# MAGI_sUSBCore.net
KiCad netlist of a schematic drawn in Altium Designer
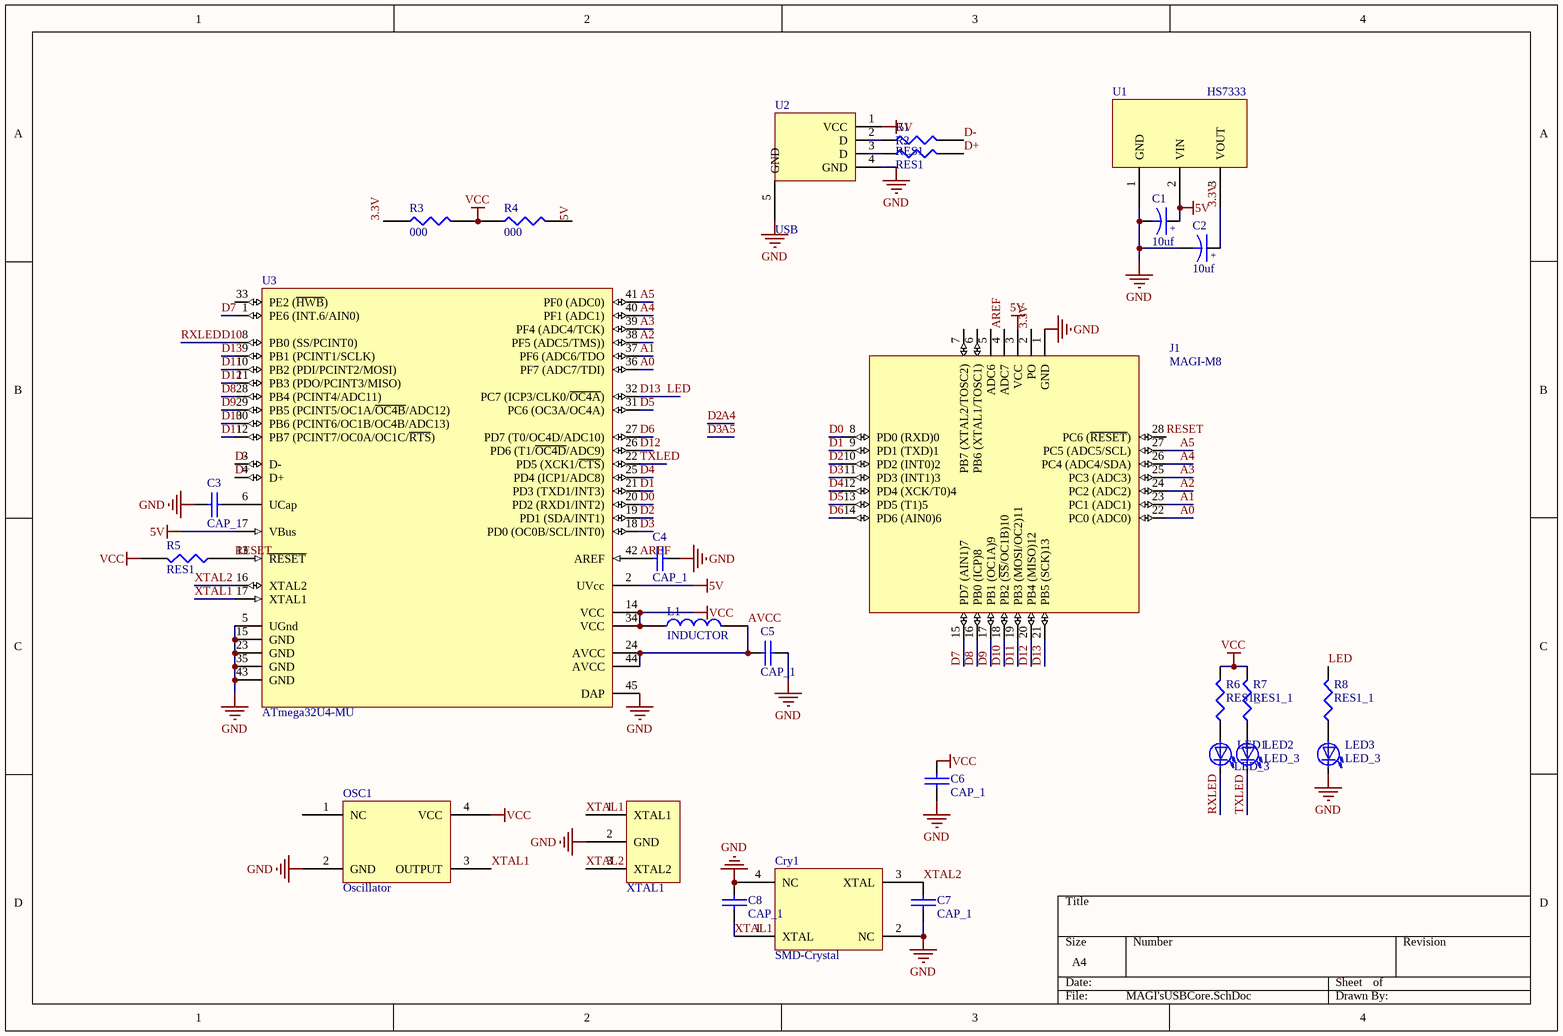
[diagram p0: MAGI'sUSBCore.SchDoc]

(export (version "E")
  (design (tool "Eeschema 10.0.6"))
  (components
    (comp (ref "C1")
      (value "10uf")
      (footprint "6-0805_N")
      (description "Capacitor")
      (libsource (lib "电容器") (part "CAPACITOR POL"))
    )
    (comp (ref "C2")
      (value "10uf")
      (footprint "6-0805_N")
      (description "Capacitor")
      (libsource (lib "电容器") (part "CAPACITOR POL"))
    )
    (comp (ref "C3")
      (value "CAP_1")
      (footprint "6-0805_N")
      (description "Capacitor")
      (libsource (lib "电容器") (part "CAP_1"))
    )
    (comp (ref "C4")
      (value "CAP_1")
      (footprint "6-0805_N")
      (description "Capacitor")
      (libsource (lib "电容器") (part "CAP_1"))
    )
    (comp (ref "C5")
      (value "CAP_1")
      (footprint "6-0805_N")
      (description "Capacitor")
      (libsource (lib "电容器") (part "CAP_1"))
    )
    (comp (ref "C6")
      (value "CAP_1")
      (footprint "C1210_N")
      (description "Capacitor")
      (libsource (lib "电容器") (part "CAP_1"))
    )
    (comp (ref "C7")
      (value "CAP_1")
      (footprint "1608[0603]")
      (description "Capacitor")
      (libsource (lib "电容器") (part "CAP_1"))
    )
    (comp (ref "C8")
      (value "CAP_1")
      (footprint "1608[0603]")
      (description "Capacitor")
      (libsource (lib "电容器") (part "CAP_1"))
    )
    (comp (ref "Cry1") (value "SMD-Crystal") (footprint "3225") (libsource (lib "XTAL") (part "Crystal")))
    (comp (ref "J1") (value "MAGI-M8") (footprint "MAGI-M8") (libsource (lib "MAGI-M8") (part "MAGI-M8")))
    (comp (ref "L1") (value "INDUCTOR") (footprint "C1210_N") (libsource (lib "汇总") (part "INDUCTOR")))
    (comp (ref "LED1") (value "LED_3") (footprint "6-0805_N") (libsource (lib "二极管") (part "LED_3")))
    (comp (ref "LED2") (value "LED_3") (footprint "6-0805_N") (libsource (lib "二极管") (part "LED_3")))
    (comp (ref "LED3") (value "LED_3") (footprint "6-0805_N") (libsource (lib "二极管") (part "LED_3")))
    (comp (ref "OSC1")
      (value "Oscillator")
      (footprint "Oscillator")
      (libsource (lib "XTAL") (part "Oscillator"))
    )
    (comp (ref "R1") (value "RES1") (footprint "6-0805_N") (libsource (lib "电阻器") (part "RES1")))
    (comp (ref "R2") (value "RES1") (footprint "6-0805_N") (libsource (lib "电阻器") (part "RES1")))
    (comp (ref "R3") (value "000") (footprint "6-0805_N") (libsource (lib "电阻器") (part "RES1")))
    (comp (ref "R4") (value "000") (footprint "6-0805_N") (libsource (lib "电阻器") (part "RES1")))
    (comp (ref "R5") (value "RES1") (footprint "6-0805_N") (libsource (lib "电阻器") (part "RES1")))
    (comp (ref "R6") (value "RES1_1") (footprint "6-0805_N") (libsource (lib "电阻器") (part "RES1_1")))
    (comp (ref "R7") (value "RES1_1") (footprint "6-0805_N") (libsource (lib "电阻器") (part "RES1_1")))
    (comp (ref "R8") (value "RES1_1") (footprint "6-0805_N") (libsource (lib "电阻器") (part "RES1_1")))
    (comp (ref "U1") (value "HS7333") (footprint "HS7333") (libsource (lib "PMIC") (part "HS7333")))
    (comp (ref "U2") (value "USB") (footprint "MicroUSB") (libsource (lib "USB接口") (part "USB")))
    (comp (ref "U3")
      (value "ATmega32U4-MU")
      (footprint "44PW_N")
      (fields (field (name "PUBLISHER") "Altium Limited"))
      (libsource (lib "Atmel Microcontroller 8-Bit megaAVR") (part "ATmega32U4-MU"))
    )
    (comp (ref "XTAL1")
      (value "CSTCE16M00G53")
      (footprint "CSTCE_V")
      (libsource (lib "XTAL") (part "CSTCE16M00G53"))
    )
  )
  (nets
    (net (code "1") (name "/3.3V") (class "Default")
      (node (ref "C2") (pin "1") (pinfunction "1_1") (pintype "passive"))
      (node (ref "J1") (pin "2") (pinfunction "PO_2") (pintype "power_in"))
      (node (ref "R3") (pin "1") (pinfunction "1_1") (pintype "passive"))
      (node (ref "U1") (pin "3") (pinfunction "VOUT_3") (pintype "passive"))
    )
    (net (code "2") (name "/A0") (class "Default")
      (node (ref "J1") (pin "22") (pinfunction "PC0_(ADC0)_22") (pintype "bidirectional"))
      (node (ref "U3") (pin "36") (pinfunction "PF7_(ADC7/TDI)_36") (pintype "bidirectional"))
    )
    (net (code "3") (name "/A1") (class "Default")
      (node (ref "J1") (pin "23") (pinfunction "PC1_(ADC1)_23") (pintype "bidirectional"))
      (node (ref "U3") (pin "37") (pinfunction "PF6_(ADC6/TDO_37") (pintype "bidirectional"))
    )
    (net (code "4") (name "/A2") (class "Default")
      (node (ref "J1") (pin "24") (pinfunction "PC2_(ADC2)_24") (pintype "bidirectional"))
      (node (ref "U3") (pin "38") (pinfunction "PF5_(ADC5/TMS))_38") (pintype "bidirectional"))
    )
    (net (code "5") (name "/A3") (class "Default")
      (node (ref "J1") (pin "25") (pinfunction "PC3_(ADC3)_25") (pintype "bidirectional"))
      (node (ref "U3") (pin "39") (pinfunction "PF4_(ADC4/TCK)_39") (pintype "bidirectional"))
    )
    (net (code "6") (name "/A4") (class "Default")
      (node (ref "J1") (pin "10") (pinfunction "PD2_(INT0)2_10") (pintype "bidirectional"))
      (node (ref "J1") (pin "26") (pinfunction "PC4_(ADC4/SDA)_26") (pintype "bidirectional"))
      (node (ref "U3") (pin "19") (pinfunction "PD1_(SDA/INT1)_19") (pintype "bidirectional"))
      (node (ref "U3") (pin "40") (pinfunction "PF1_(ADC1)_40") (pintype "bidirectional"))
    )
    (net (code "7") (name "/A5") (class "Default")
      (node (ref "J1") (pin "11") (pinfunction "PD3_(INT1)3_11") (pintype "bidirectional"))
      (node (ref "J1") (pin "27") (pinfunction "PC5_(ADC5/SCL)_27") (pintype "bidirectional"))
      (node (ref "U3") (pin "18") (pinfunction "PD0_(OC0B/SCL/INT0)_18") (pintype "bidirectional"))
      (node (ref "U3") (pin "41") (pinfunction "PF0_(ADC0)_41") (pintype "bidirectional"))
    )
    (net (code "8") (name "/AREF") (class "Default")
      (node (ref "C4") (pin "2") (pinfunction "2_2") (pintype "passive"))
      (node (ref "J1") (pin "4") (pinfunction "ADC7_4") (pintype "passive"))
      (node (ref "U3") (pin "42") (pinfunction "AREF_42") (pintype "input"))
    )
    (net (code "9") (name "/AVCC") (class "Default")
      (node (ref "C5") (pin "2") (pinfunction "2_2") (pintype "passive"))
      (node (ref "L1") (pin "1") (pinfunction "1_1") (pintype "passive"))
      (node (ref "U3") (pin "24") (pinfunction "AVCC_24") (pintype "power_in"))
      (node (ref "U3") (pin "44") (pinfunction "AVCC_44") (pintype "power_in"))
    )
    (net (code "10") (name "/D+") (class "Default")
      (node (ref "R2") (pin "2") (pinfunction "2_2") (pintype "passive"))
      (node (ref "U3") (pin "4") (pinfunction "D+_4") (pintype "bidirectional"))
    )
    (net (code "11") (name "/D-") (class "Default")
      (node (ref "R1") (pin "2") (pinfunction "2_2") (pintype "passive"))
      (node (ref "U3") (pin "3") (pinfunction "D-_3") (pintype "bidirectional"))
    )
    (net (code "12") (name "/D0") (class "Default")
      (node (ref "J1") (pin "8") (pinfunction "PD0_(RXD)0_8") (pintype "bidirectional"))
      (node (ref "U3") (pin "20") (pinfunction "PD2_(RXD1/INT2)_20") (pintype "bidirectional"))
    )
    (net (code "13") (name "/D1") (class "Default")
      (node (ref "J1") (pin "9") (pinfunction "PD1_(TXD)1_9") (pintype "bidirectional"))
      (node (ref "U3") (pin "21") (pinfunction "PD3_(TXD1/INT3)_21") (pintype "bidirectional"))
    )
    (net (code "14") (name "/D4") (class "Default")
      (node (ref "J1") (pin "12") (pinfunction "PD4_(XCK/T0)4_12") (pintype "bidirectional"))
      (node (ref "U3") (pin "25") (pinfunction "PD4_(ICP1/ADC8)_25") (pintype "bidirectional"))
    )
    (net (code "15") (name "/D5") (class "Default")
      (node (ref "J1") (pin "13") (pinfunction "PD5_(T1)5_13") (pintype "bidirectional"))
      (node (ref "U3") (pin "31") (pinfunction "PC6_(OC3A/OC4A)_31") (pintype "bidirectional"))
    )
    (net (code "16") (name "/D6") (class "Default")
      (node (ref "J1") (pin "14") (pinfunction "PD6_(AIN0)6_14") (pintype "bidirectional"))
      (node (ref "U3") (pin "27") (pinfunction "PD7_(T0/OC4D/ADC10)_27") (pintype "bidirectional"))
    )
    (net (code "17") (name "/D7") (class "Default")
      (node (ref "J1") (pin "15") (pinfunction "PD7_(AIN1)7_15") (pintype "bidirectional"))
      (node (ref "U3") (pin "1") (pinfunction "PE6_(INT.6/AIN0)_1") (pintype "bidirectional"))
    )
    (net (code "18") (name "/D8") (class "Default")
      (node (ref "J1") (pin "16") (pinfunction "PB0_(ICP)8_16") (pintype "bidirectional"))
      (node (ref "U3") (pin "28") (pinfunction "PB4_(PCINT4/ADC11)_28") (pintype "bidirectional"))
    )
    (net (code "19") (name "/D9") (class "Default")
      (node (ref "J1") (pin "17") (pinfunction "PB1_(OC1A)9_17") (pintype "bidirectional"))
      (node (ref "U3") (pin "29") (pinfunction "PB5_(PCINT5/OC1A/~{OC4B}/ADC12)_29") (pintype "bidirectional"))
    )
    (net (code "20") (name "/D10") (class "Default")
      (node (ref "J1") (pin "18") (pinfunction "PB2_(~{SS}/OC1B)10_18") (pintype "bidirectional"))
      (node (ref "LED1") (pin "2") (pinfunction "K_2") (pintype "passive"))
      (node (ref "U3") (pin "30") (pinfunction "PB6_(PCINT6/OC1B/OC4B/ADC13)_30") (pintype "bidirectional"))
      (node (ref "U3") (pin "8") (pinfunction "PB0_(SS/PCINT0)_8") (pintype "bidirectional"))
    )
    (net (code "21") (name "/D11") (class "Default")
      (node (ref "J1") (pin "19") (pinfunction "PB3_(MOSI/OC2)11_19") (pintype "bidirectional"))
      (node (ref "U3") (pin "10") (pinfunction "PB2_(PDI/PCINT2/MOSI)_10") (pintype "bidirectional"))
      (node (ref "U3") (pin "12") (pinfunction "PB7_(PCINT7/OC0A/OC1C/~{RTS})_12") (pintype "bidirectional"))
    )
    (net (code "22") (name "/D12") (class "Default")
      (node (ref "J1") (pin "20") (pinfunction "PB4_(MISO)12_20") (pintype "bidirectional"))
      (node (ref "U3") (pin "11") (pinfunction "PB3_(PDO/PCINT3/MISO)_11") (pintype "bidirectional"))
      (node (ref "U3") (pin "26") (pinfunction "PD6_(T1/~{OC4D}/ADC9)_26") (pintype "bidirectional"))
    )
    (net (code "23") (name "/D13") (class "Default")
      (node (ref "J1") (pin "21") (pinfunction "PB5_(SCK)13_21") (pintype "bidirectional"))
      (node (ref "R8") (pin "2") (pinfunction "2_2") (pintype "passive"))
      (node (ref "U3") (pin "32") (pinfunction "PC7_(ICP3/CLK0/~{OC4A})_32") (pintype "bidirectional"))
      (node (ref "U3") (pin "9") (pinfunction "PB1_(PCINT1/SCLK)_9") (pintype "bidirectional"))
    )
    (net (code "24") (name "/RESET") (class "Default")
      (node (ref "J1") (pin "28") (pinfunction "PC6_(~{RESET})_28") (pintype "bidirectional"))
      (node (ref "R5") (pin "1") (pinfunction "1_1") (pintype "passive"))
      (node (ref "U3") (pin "13") (pinfunction "~{RESET}_13") (pintype "input"))
    )
    (net (code "25") (name "/TXLED") (class "Default")
      (node (ref "LED2") (pin "2") (pinfunction "K_2") (pintype "passive"))
      (node (ref "U3") (pin "22") (pinfunction "PD5_(XCK1/~{CTS})_22") (pintype "bidirectional"))
    )
    (net (code "26") (name "/XTAL1") (class "Default")
      (node (ref "C8") (pin "1") (pinfunction "1_1") (pintype "passive"))
      (node (ref "Cry1") (pin "1") (pinfunction "XTAL_1") (pintype "passive"))
      (node (ref "OSC1") (pin "3") (pinfunction "OUTPUT_3") (pintype "passive"))
      (node (ref "U3") (pin "17") (pinfunction "XTAL1_17") (pintype "input"))
      (node (ref "XTAL1") (pin "1") (pinfunction "XTAL1_1") (pintype "passive"))
    )
    (net (code "27") (name "/XTAL2") (class "Default")
      (node (ref "C7") (pin "2") (pinfunction "2_2") (pintype "passive"))
      (node (ref "Cry1") (pin "3") (pinfunction "XTAL_3") (pintype "passive"))
      (node (ref "U3") (pin "16") (pinfunction "XTAL2_16") (pintype "bidirectional"))
      (node (ref "XTAL1") (pin "3") (pinfunction "XTAL2_3") (pintype "passive"))
    )
    (net (code "28") (name "5V") (class "Default")
      (node (ref "C1") (pin "1") (pinfunction "1_1") (pintype "passive"))
      (node (ref "J1") (pin "3") (pinfunction "VCC_3") (pintype "power_in"))
      (node (ref "R4") (pin "2") (pinfunction "2_2") (pintype "passive"))
      (node (ref "U1") (pin "2") (pinfunction "VIN_2") (pintype "passive"))
      (node (ref "U2") (pin "1") (pinfunction "VCC_1") (pintype "passive"))
      (node (ref "U3") (pin "2") (pinfunction "UVcc_2") (pintype "power_in"))
      (node (ref "U3") (pin "7") (pinfunction "VBus_7") (pintype "input"))
    )
    (net (code "29") (name "GND") (class "Default")
      (node (ref "C1") (pin "2") (pinfunction "2_2") (pintype "passive"))
      (node (ref "C2") (pin "2") (pinfunction "2_2") (pintype "passive"))
      (node (ref "C3") (pin "2") (pinfunction "2_2") (pintype "passive"))
      (node (ref "C4") (pin "1") (pinfunction "1_1") (pintype "passive"))
      (node (ref "C5") (pin "1") (pinfunction "1_1") (pintype "passive"))
      (node (ref "C6") (pin "1") (pinfunction "1_1") (pintype "passive"))
      (node (ref "C7") (pin "1") (pinfunction "1_1") (pintype "passive"))
      (node (ref "C8") (pin "2") (pinfunction "2_2") (pintype "passive"))
      (node (ref "Cry1") (pin "2") (pinfunction "NC_2") (pintype "passive"))
      (node (ref "Cry1") (pin "4") (pinfunction "NC_4") (pintype "passive"))
      (node (ref "J1") (pin "1") (pinfunction "GND_1") (pintype "power_in"))
      (node (ref "LED3") (pin "2") (pinfunction "K_2") (pintype "passive"))
      (node (ref "OSC1") (pin "2") (pinfunction "GND_2") (pintype "passive"))
      (node (ref "U1") (pin "1") (pinfunction "GND_1") (pintype "passive"))
      (node (ref "U2") (pin "4") (pinfunction "GND_4") (pintype "passive"))
      (node (ref "U2") (pin "5") (pinfunction "GND_5") (pintype "passive"))
      (node (ref "U3") (pin "15") (pinfunction "GND_15") (pintype "power_in"))
      (node (ref "U3") (pin "23") (pinfunction "GND_23") (pintype "power_in"))
      (node (ref "U3") (pin "35") (pinfunction "GND_35") (pintype "power_in"))
      (node (ref "U3") (pin "43") (pinfunction "GND_43") (pintype "power_in"))
      (node (ref "U3") (pin "45") (pinfunction "DAP_45") (pintype "power_in"))
      (node (ref "U3") (pin "5") (pinfunction "UGnd_5") (pintype "power_in"))
      (node (ref "XTAL1") (pin "2") (pinfunction "GND_2") (pintype "passive"))
    )
    (net (code "30") (name "Net-(LED1-A)") (class "Default")
      (node (ref "LED1") (pin "1") (pinfunction "A_1") (pintype "passive"))
      (node (ref "R6") (pin "1") (pinfunction "1_1") (pintype "passive"))
    )
    (net (code "31") (name "Net-(LED2-A)") (class "Default")
      (node (ref "LED2") (pin "1") (pinfunction "A_1") (pintype "passive"))
      (node (ref "R7") (pin "1") (pinfunction "1_1") (pintype "passive"))
    )
    (net (code "32") (name "Net-(LED3-A)") (class "Default")
      (node (ref "LED3") (pin "1") (pinfunction "A_1") (pintype "passive"))
      (node (ref "R8") (pin "1") (pinfunction "1_1") (pintype "passive"))
    )
    (net (code "33") (name "Net-(R1-Pad1)") (class "Default")
      (node (ref "R1") (pin "1") (pinfunction "1_1") (pintype "passive"))
      (node (ref "U2") (pin "2") (pinfunction "D_2") (pintype "passive"))
    )
    (net (code "34") (name "Net-(R2-Pad1)") (class "Default")
      (node (ref "R2") (pin "1") (pinfunction "1_1") (pintype "passive"))
      (node (ref "U2") (pin "3") (pinfunction "D_3") (pintype "passive"))
    )
    (net (code "35") (name "Net-(U3-UCap)") (class "Default")
      (node (ref "C3") (pin "1") (pinfunction "1_1") (pintype "passive"))
      (node (ref "U3") (pin "6") (pinfunction "UCap_6") (pintype "passive"))
    )
    (net (code "36") (name "VCC") (class "Default")
      (node (ref "C6") (pin "2") (pinfunction "2_2") (pintype "passive"))
      (node (ref "L1") (pin "2") (pinfunction "2_2") (pintype "passive"))
      (node (ref "OSC1") (pin "4") (pinfunction "VCC_4") (pintype "passive"))
      (node (ref "R3") (pin "2") (pinfunction "2_2") (pintype "passive"))
      (node (ref "R4") (pin "1") (pinfunction "1_1") (pintype "passive"))
      (node (ref "R5") (pin "2") (pinfunction "2_2") (pintype "passive"))
      (node (ref "R6") (pin "2") (pinfunction "2_2") (pintype "passive"))
      (node (ref "R7") (pin "2") (pinfunction "2_2") (pintype "passive"))
      (node (ref "U3") (pin "14") (pinfunction "VCC_14") (pintype "power_in"))
      (node (ref "U3") (pin "34") (pinfunction "VCC_34") (pintype "power_in"))
    )
    (net (code "37") (name "unconnected-(J1-ADC6-Pad5)") (class "Default")
      (node (ref "J1") (pin "5") (pinfunction "ADC6_5") (pintype "passive"))
    )
    (net (code "38") (name "unconnected-(J1-PB6_(XTAL1{slash}TOSC1)-Pad6)") (class "Default")
      (node (ref "J1") (pin "6") (pinfunction "PB6_(XTAL1/TOSC1)_6") (pintype "bidirectional"))
    )
    (net (code "39") (name "unconnected-(J1-PB7_(XTAL2{slash}TOSC2)-Pad7)") (class "Default")
      (node (ref "J1") (pin "7") (pinfunction "PB7_(XTAL2/TOSC2)_7") (pintype "bidirectional"))
    )
    (net (code "40") (name "unconnected-(OSC1-NC-Pad1)") (class "Default")
      (node (ref "OSC1") (pin "1") (pinfunction "NC_1") (pintype "passive"))
    )
    (net (code "41") (name "unconnected-(U3-PE2_(~{HWB})-Pad33)") (class "Default")
      (node (ref "U3") (pin "33") (pinfunction "PE2_(~{HWB})_33") (pintype "bidirectional"))
    )
  )
)
